# conditioning_circuit.net
KiCad netlist of a schematic drawn in Altium Designer
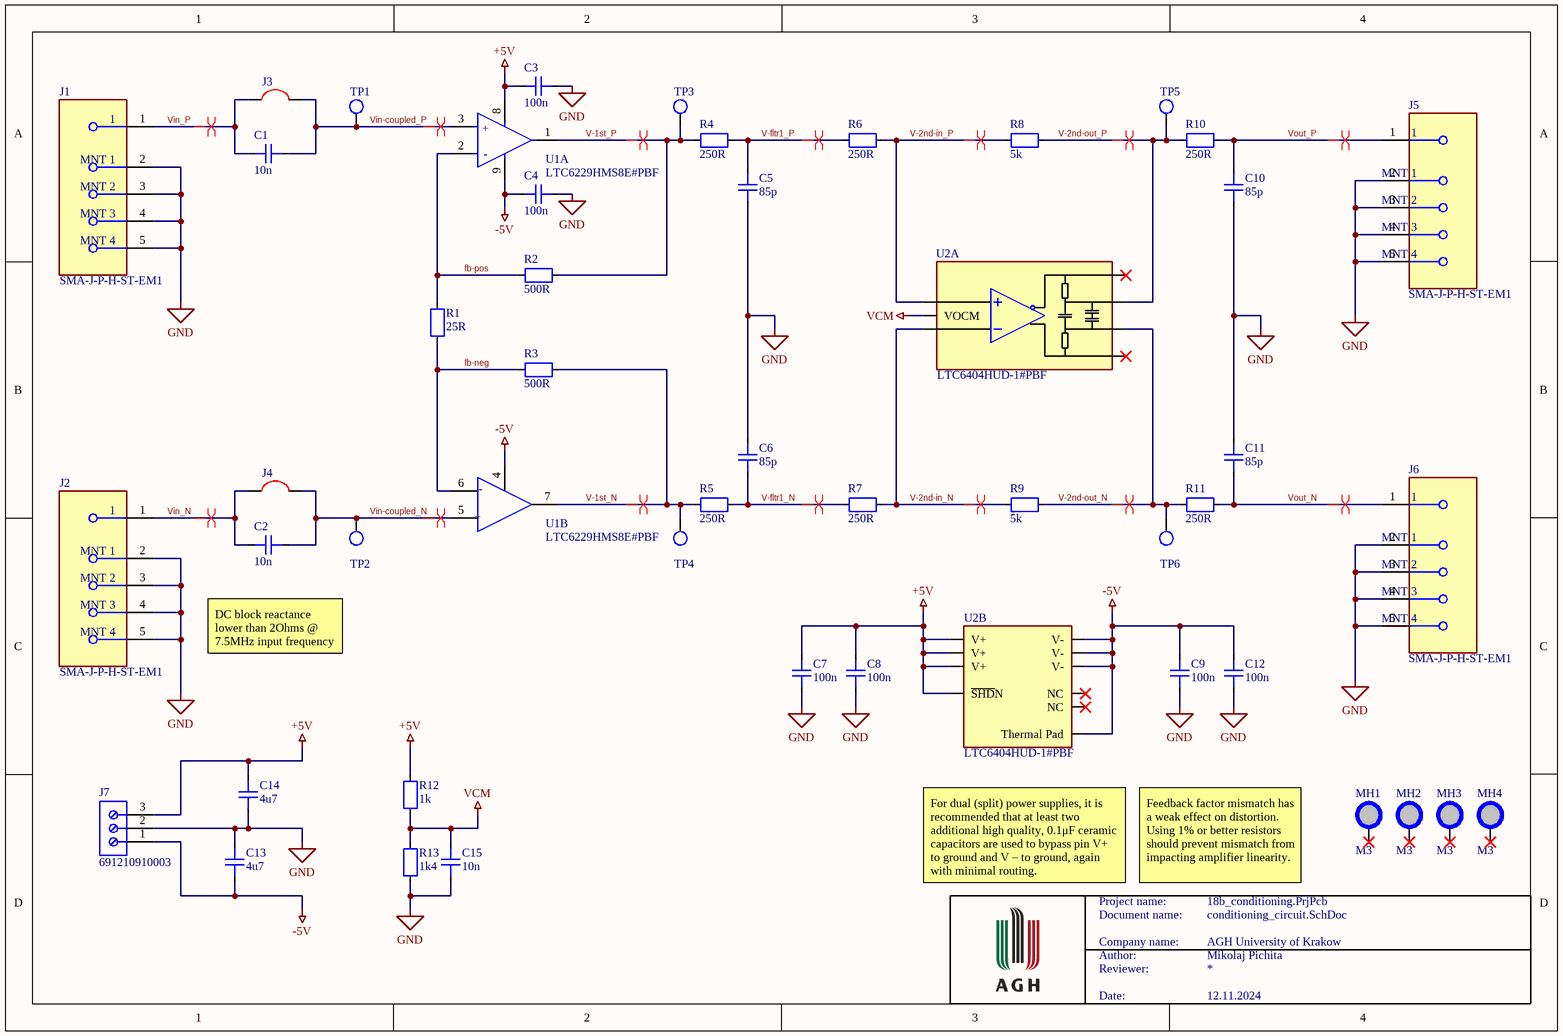
[diagram p0: conditioning_circuit.SchDoc]

(export (version "E")
  (design (tool "Eeschema 10.0.6"))
  (components
    (comp (ref "C1")
      (value "10n")
      (footprint "CAP0603")
      (libsource (lib "Integrated_Library_main") (part "Capacitor"))
    )
    (comp (ref "C2")
      (value "10n")
      (footprint "CAP0603")
      (libsource (lib "Integrated_Library_main") (part "Capacitor"))
    )
    (comp (ref "C3")
      (value "100n")
      (footprint "CAP0603")
      (libsource (lib "Integrated_Library_main") (part "Capacitor"))
    )
    (comp (ref "C4")
      (value "100n")
      (footprint "CAP0603")
      (libsource (lib "Integrated_Library_main") (part "Capacitor"))
    )
    (comp (ref "C5")
      (value "85p")
      (footprint "CAP0603")
      (libsource (lib "Integrated_Library_main") (part "Capacitor"))
    )
    (comp (ref "C6")
      (value "85p")
      (footprint "CAP0603")
      (libsource (lib "Integrated_Library_main") (part "Capacitor"))
    )
    (comp (ref "C7")
      (value "100n")
      (footprint "CAP0603")
      (libsource (lib "Integrated_Library_main") (part "Capacitor"))
    )
    (comp (ref "C8")
      (value "100n")
      (footprint "CAP0603")
      (libsource (lib "Integrated_Library_main") (part "Capacitor"))
    )
    (comp (ref "C9")
      (value "100n")
      (footprint "CAP0603")
      (libsource (lib "Integrated_Library_main") (part "Capacitor"))
    )
    (comp (ref "C10")
      (value "85p")
      (footprint "CAP0603")
      (libsource (lib "Integrated_Library_main") (part "Capacitor"))
    )
    (comp (ref "C11")
      (value "85p")
      (footprint "CAP0603")
      (libsource (lib "Integrated_Library_main") (part "Capacitor"))
    )
    (comp (ref "C12")
      (value "100n")
      (footprint "CAP0603")
      (libsource (lib "Integrated_Library_main") (part "Capacitor"))
    )
    (comp (ref "C13")
      (value "4u7")
      (footprint "CAP0603")
      (libsource (lib "Integrated_Library_main") (part "Capacitor"))
    )
    (comp (ref "C14")
      (value "4u7")
      (footprint "CAP0603")
      (libsource (lib "Integrated_Library_main") (part "Capacitor"))
    )
    (comp (ref "C15")
      (value "10n")
      (footprint "CAP0603")
      (libsource (lib "Integrated_Library_main") (part "Capacitor"))
    )
    (comp (ref "J1")
      (value "SMA-J-P-H-ST-EM1")
      (footprint "FP-SMA-J-P-H-ST-EM1-MFG")
      (description "CONN SMA JACK STR 50OHM EDGE MNT")
      (libsource (lib "Altium Content Vault") (part "c65b8a639cdaef1819ea20b5466f8fa"))
    )
    (comp (ref "J2")
      (value "SMA-J-P-H-ST-EM1")
      (footprint "FP-SMA-J-P-H-ST-EM1-MFG")
      (description "CONN SMA JACK STR 50OHM EDGE MNT")
      (libsource (lib "Altium Content Vault") (part "c65b8a639cdaef1819ea20b5466f8fa"))
    )
    (comp (ref "J3")
      (value "*")
      (footprint "JUMPER")
      (libsource (lib "Integrated_Library_main") (part "Jumper"))
    )
    (comp (ref "J4")
      (value "*")
      (footprint "JUMPER")
      (libsource (lib "Integrated_Library_main") (part "Jumper"))
    )
    (comp (ref "J5")
      (value "SMA-J-P-H-ST-EM1")
      (footprint "FP-SMA-J-P-H-ST-EM1-MFG")
      (description "CONN SMA JACK STR 50OHM EDGE MNT")
      (libsource (lib "") (part "c65b8a639cdaef1819ea20b5466f8fa_1"))
    )
    (comp (ref "J6")
      (value "SMA-J-P-H-ST-EM1")
      (footprint "FP-SMA-J-P-H-ST-EM1-MFG")
      (description "CONN SMA JACK STR 50OHM EDGE MNT")
      (libsource (lib "") (part "c65b8a639cdaef1819ea20b5466f8fa_1"))
    )
    (comp (ref "J7")
      (value "691210910003")
      (footprint "691210910003")
      (libsource (lib "Altium Content Vault") (part "TBL - 1R - 03P - Screw"))
    )
    (comp (ref "MH1")
      (value "M3")
      (footprint "MountingHole")
      (libsource (lib "Integrated_Library_main") (part "Mounting hole"))
    )
    (comp (ref "MH2")
      (value "M3")
      (footprint "MountingHole")
      (libsource (lib "Integrated_Library_main") (part "Mounting hole"))
    )
    (comp (ref "MH3")
      (value "M3")
      (footprint "MountingHole")
      (libsource (lib "Integrated_Library_main") (part "Mounting hole"))
    )
    (comp (ref "MH4")
      (value "M3")
      (footprint "MountingHole")
      (libsource (lib "Integrated_Library_main") (part "Mounting hole"))
    )
    (comp (ref "R1")
      (value "25R")
      (footprint "RES0603")
      (libsource (lib "Integrated_Library_main") (part "Resistor"))
    )
    (comp (ref "R2")
      (value "500R")
      (footprint "RES0603")
      (libsource (lib "Integrated_Library_main") (part "Resistor"))
    )
    (comp (ref "R3")
      (value "500R")
      (footprint "RES0603")
      (libsource (lib "Integrated_Library_main") (part "Resistor"))
    )
    (comp (ref "R4")
      (value "250R")
      (footprint "RES0603")
      (libsource (lib "Integrated_Library_main") (part "Resistor"))
    )
    (comp (ref "R5")
      (value "250R")
      (footprint "RES0603")
      (libsource (lib "Integrated_Library_main") (part "Resistor"))
    )
    (comp (ref "R6")
      (value "250R")
      (footprint "RES0603")
      (libsource (lib "Integrated_Library_main") (part "Resistor"))
    )
    (comp (ref "R7")
      (value "250R")
      (footprint "RES0603")
      (libsource (lib "Integrated_Library_main") (part "Resistor"))
    )
    (comp (ref "R8")
      (value "5k")
      (footprint "RES0603")
      (libsource (lib "Integrated_Library_main") (part "Resistor"))
    )
    (comp (ref "R9")
      (value "5k")
      (footprint "RES0603")
      (libsource (lib "Integrated_Library_main") (part "Resistor"))
    )
    (comp (ref "R10")
      (value "250R")
      (footprint "RES0603")
      (libsource (lib "Integrated_Library_main") (part "Resistor"))
    )
    (comp (ref "R11")
      (value "250R")
      (footprint "RES0603")
      (libsource (lib "Integrated_Library_main") (part "Resistor"))
    )
    (comp (ref "R12")
      (value "1k")
      (footprint "RES0603")
      (libsource (lib "Integrated_Library_main") (part "Resistor"))
    )
    (comp (ref "R13")
      (value "1k4")
      (footprint "RES0603")
      (libsource (lib "Integrated_Library_main") (part "Resistor"))
    )
    (comp (ref "TP1")
      (value "Testpoint")
      (footprint "SMD_TESTPOINT")
      (libsource (lib "Integrated_Library_main") (part "SMD_testpoint"))
    )
    (comp (ref "TP2")
      (value "Testpoint")
      (footprint "SMD_TESTPOINT")
      (libsource (lib "Integrated_Library_main") (part "SMD_testpoint"))
    )
    (comp (ref "TP3")
      (value "Testpoint")
      (footprint "SMD_TESTPOINT")
      (libsource (lib "Integrated_Library_main") (part "SMD_testpoint"))
    )
    (comp (ref "TP4")
      (value "Testpoint")
      (footprint "SMD_TESTPOINT")
      (libsource (lib "Integrated_Library_main") (part "SMD_testpoint"))
    )
    (comp (ref "TP5")
      (value "Testpoint")
      (footprint "SMD_TESTPOINT")
      (libsource (lib "Integrated_Library_main") (part "SMD_testpoint"))
    )
    (comp (ref "TP6")
      (value "Testpoint")
      (footprint "SMD_TESTPOINT")
      (libsource (lib "Integrated_Library_main") (part "SMD_testpoint"))
    )
    (comp (ref "U1")
      (value "LTC6229HMS8E#PBF")
      (footprint "FP-MS8E-8-05-08-1662-IPC_C")
      (description "IC OPAMP GP 1 CIRCUIT 8MSOP")
      (libsource (lib "Altium Content Vault") (part "d9671d919594e6673b65f0ad0d835fa"))
    )
    (comp (ref "U2")
      (value "LTC6404HUD-1#PBF")
      (footprint "LT-UD-16_M")
      (description "High Speed Operational Amplifiers 600MHz, L N, Hi Prec Fully Diff In/Out A")
      (libsource (lib "") (part "LTC6404HUD-1#PBF_1"))
    )
  )
  (nets
    (net (code "1") (name "+5V") (class "Default")
      (node (ref "C14") (pin "1") (pintype "passive"))
      (node (ref "C3") (pin "1") (pintype "passive"))
      (node (ref "C7") (pin "1") (pintype "passive"))
      (node (ref "C8") (pin "1") (pintype "passive"))
      (node (ref "J7") (pin "3") (pinfunction "3_3") (pintype "passive"))
      (node (ref "R12") (pin "2") (pintype "passive"))
      (node (ref "U1") (pin "8") (pinfunction "V+_8") (pintype "power_in"))
      (node (ref "U2") (pin "1") (pinfunction "~{SHD}N_1") (pintype "passive"))
      (node (ref "U2") (pin "10") (pinfunction "V+_10") (pintype "passive"))
      (node (ref "U2") (pin "11") (pinfunction "V+_11") (pintype "passive"))
      (node (ref "U2") (pin "2") (pinfunction "V+_2") (pintype "passive"))
    )
    (net (code "2") (name "-5V") (class "Default")
      (node (ref "C12") (pin "1") (pintype "passive"))
      (node (ref "C13") (pin "2") (pintype "passive"))
      (node (ref "C4") (pin "1") (pintype "passive"))
      (node (ref "C9") (pin "1") (pintype "passive"))
      (node (ref "J7") (pin "1") (pinfunction "1_1") (pintype "passive"))
      (node (ref "U1") (pin "4") (pinfunction "V-_4") (pintype "power_in"))
      (node (ref "U1") (pin "9") (pinfunction "V-_9") (pintype "power_in"))
      (node (ref "U2") (pin "12") (pinfunction "V-_12") (pintype "passive"))
      (node (ref "U2") (pin "17") (pinfunction "Thermal_Pad_17") (pintype "passive"))
      (node (ref "U2") (pin "3") (pinfunction "V-_3") (pintype "passive"))
      (node (ref "U2") (pin "9") (pinfunction "V-_9") (pintype "passive"))
    )
    (net (code "3") (name "/V-1st_N") (class "Default")
      (node (ref "R3") (pin "2") (pintype "passive"))
      (node (ref "R5") (pin "2") (pintype "passive"))
      (node (ref "TP4") (pin "1") (pintype "passive"))
      (node (ref "U1") (pin "7") (pinfunction "OUTB_7") (pintype "passive"))
    )
    (net (code "4") (name "/V-1st_P") (class "Default")
      (node (ref "R2") (pin "2") (pintype "passive"))
      (node (ref "R4") (pin "1") (pintype "passive"))
      (node (ref "TP3") (pin "1") (pintype "passive"))
      (node (ref "U1") (pin "1") (pinfunction "OUTA_1") (pintype "passive"))
    )
    (net (code "5") (name "/V-2nd-in_N") (class "Default")
      (node (ref "R7") (pin "1") (pintype "passive"))
      (node (ref "R9") (pin "1") (pintype "passive"))
      (node (ref "U2") (pin "6") (pinfunction "IN-_6") (pintype "passive"))
    )
    (net (code "6") (name "/V-2nd-in_P") (class "Default")
      (node (ref "R6") (pin "2") (pintype "passive"))
      (node (ref "R8") (pin "1") (pintype "passive"))
      (node (ref "U2") (pin "15") (pinfunction "IN+_15") (pintype "passive"))
    )
    (net (code "7") (name "/V-2nd-out_N") (class "Default")
      (node (ref "R11") (pin "2") (pintype "passive"))
      (node (ref "R9") (pin "2") (pintype "passive"))
      (node (ref "TP6") (pin "1") (pintype "passive"))
      (node (ref "U2") (pin "7") (pinfunction "OUT+_7") (pintype "passive"))
    )
    (net (code "8") (name "/V-2nd-out_P") (class "Default")
      (node (ref "R10") (pin "1") (pintype "passive"))
      (node (ref "R8") (pin "2") (pintype "passive"))
      (node (ref "TP5") (pin "1") (pintype "passive"))
      (node (ref "U2") (pin "14") (pinfunction "OUT-_14") (pintype "passive"))
    )
    (net (code "9") (name "/V-fltr1_N") (class "Default")
      (node (ref "C6") (pin "2") (pintype "passive"))
      (node (ref "R5") (pin "1") (pintype "passive"))
      (node (ref "R7") (pin "2") (pintype "passive"))
    )
    (net (code "10") (name "/V-fltr1_P") (class "Default")
      (node (ref "C5") (pin "2") (pintype "passive"))
      (node (ref "R4") (pin "2") (pintype "passive"))
      (node (ref "R6") (pin "1") (pintype "passive"))
    )
    (net (code "11") (name "/Vin-coupled_N") (class "Default")
      (node (ref "C2") (pin "2") (pintype "passive"))
      (node (ref "J4") (pin "2") (pinfunction "2_2") (pintype "passive"))
      (node (ref "TP2") (pin "1") (pintype "passive"))
      (node (ref "U1") (pin "5") (pinfunction "+INB_5") (pintype "tri_state"))
    )
    (net (code "12") (name "/Vin-coupled_P") (class "Default")
      (node (ref "C1") (pin "2") (pintype "passive"))
      (node (ref "J3") (pin "2") (pinfunction "2_2") (pintype "passive"))
      (node (ref "TP1") (pin "1") (pintype "passive"))
      (node (ref "U1") (pin "3") (pinfunction "+IN_A_3") (pintype "tri_state"))
    )
    (net (code "13") (name "/Vin_N") (class "Default")
      (node (ref "C2") (pin "1") (pintype "passive"))
      (node (ref "J2") (pin "1") (pinfunction "1_1") (pintype "passive"))
      (node (ref "J4") (pin "1") (pinfunction "1_1") (pintype "passive"))
    )
    (net (code "14") (name "/Vin_P") (class "Default")
      (node (ref "C1") (pin "1") (pintype "passive"))
      (node (ref "J1") (pin "1") (pinfunction "1_1") (pintype "passive"))
      (node (ref "J3") (pin "1") (pinfunction "1_1") (pintype "passive"))
    )
    (net (code "15") (name "/Vout_N") (class "Default")
      (node (ref "C11") (pin "2") (pintype "passive"))
      (node (ref "J6") (pin "1") (pinfunction "1_1") (pintype "passive"))
      (node (ref "R11") (pin "1") (pintype "passive"))
    )
    (net (code "16") (name "/Vout_P") (class "Default")
      (node (ref "C10") (pin "2") (pintype "passive"))
      (node (ref "J5") (pin "1") (pinfunction "1_1") (pintype "passive"))
      (node (ref "R10") (pin "2") (pintype "passive"))
    )
    (net (code "17") (name "/fb-neg") (class "Default")
      (node (ref "R1") (pin "2") (pintype "passive"))
      (node (ref "R3") (pin "1") (pintype "passive"))
      (node (ref "U1") (pin "6") (pinfunction "-INB_6") (pintype "tri_state"))
    )
    (net (code "18") (name "/fb-pos") (class "Default")
      (node (ref "R1") (pin "1") (pintype "passive"))
      (node (ref "R2") (pin "1") (pintype "passive"))
      (node (ref "U1") (pin "2") (pinfunction "-IN_A_2") (pintype "tri_state"))
    )
    (net (code "19") (name "GND") (class "Default")
      (node (ref "C10") (pin "1") (pintype "passive"))
      (node (ref "C11") (pin "1") (pintype "passive"))
      (node (ref "C12") (pin "2") (pintype "passive"))
      (node (ref "C13") (pin "1") (pintype "passive"))
      (node (ref "C14") (pin "2") (pintype "passive"))
      (node (ref "C15") (pin "2") (pintype "passive"))
      (node (ref "C3") (pin "2") (pintype "passive"))
      (node (ref "C4") (pin "2") (pintype "passive"))
      (node (ref "C5") (pin "1") (pintype "passive"))
      (node (ref "C6") (pin "1") (pintype "passive"))
      (node (ref "C7") (pin "2") (pintype "passive"))
      (node (ref "C8") (pin "2") (pintype "passive"))
      (node (ref "C9") (pin "2") (pintype "passive"))
      (node (ref "J1") (pin "2") (pinfunction "MNT_1_2") (pintype "passive"))
      (node (ref "J1") (pin "3") (pinfunction "MNT_2_3") (pintype "passive"))
      (node (ref "J1") (pin "4") (pinfunction "MNT_3_4") (pintype "passive"))
      (node (ref "J1") (pin "5") (pinfunction "MNT_4_5") (pintype "passive"))
      (node (ref "J2") (pin "2") (pinfunction "MNT_1_2") (pintype "passive"))
      (node (ref "J2") (pin "3") (pinfunction "MNT_2_3") (pintype "passive"))
      (node (ref "J2") (pin "4") (pinfunction "MNT_3_4") (pintype "passive"))
      (node (ref "J2") (pin "5") (pinfunction "MNT_4_5") (pintype "passive"))
      (node (ref "J5") (pin "2") (pinfunction "MNT_1_2") (pintype "passive"))
      (node (ref "J5") (pin "3") (pinfunction "MNT_2_3") (pintype "passive"))
      (node (ref "J5") (pin "4") (pinfunction "MNT_3_4") (pintype "passive"))
      (node (ref "J5") (pin "5") (pinfunction "MNT_4_5") (pintype "passive"))
      (node (ref "J6") (pin "2") (pinfunction "MNT_1_2") (pintype "passive"))
      (node (ref "J6") (pin "3") (pinfunction "MNT_2_3") (pintype "passive"))
      (node (ref "J6") (pin "4") (pinfunction "MNT_3_4") (pintype "passive"))
      (node (ref "J6") (pin "5") (pinfunction "MNT_4_5") (pintype "passive"))
      (node (ref "J7") (pin "2") (pinfunction "2_2") (pintype "passive"))
      (node (ref "R13") (pin "1") (pintype "passive"))
    )
    (net (code "20") (name "VCM") (class "Default")
      (node (ref "C15") (pin "1") (pintype "passive"))
      (node (ref "R12") (pin "1") (pintype "passive"))
      (node (ref "R13") (pin "2") (pintype "passive"))
      (node (ref "U2") (pin "4") (pinfunction "VOCM_4") (pintype "passive"))
    )
    (net (code "21") (name "unconnected-(MH1-Pad1)") (class "Default")
      (node (ref "MH1") (pin "1") (pintype "passive+no_connect"))
    )
    (net (code "22") (name "unconnected-(MH2-Pad1)") (class "Default")
      (node (ref "MH2") (pin "1") (pintype "passive+no_connect"))
    )
    (net (code "23") (name "unconnected-(MH3-Pad1)") (class "Default")
      (node (ref "MH3") (pin "1") (pintype "passive+no_connect"))
    )
    (net (code "24") (name "unconnected-(MH4-Pad1)") (class "Default")
      (node (ref "MH4") (pin "1") (pintype "passive+no_connect"))
    )
    (net (code "25") (name "unconnected-(U2A-OUTF+-Pad8)") (class "Default")
      (node (ref "U2") (pin "8") (pinfunction "OUTF+_8") (pintype "passive+no_connect"))
    )
    (net (code "26") (name "unconnected-(U2A-OUTF--Pad13)") (class "Default")
      (node (ref "U2") (pin "13") (pinfunction "OUTF-_13") (pintype "passive+no_connect"))
    )
    (net (code "27") (name "unconnected-(U2B-NC-Pad5)") (class "Default")
      (node (ref "U2") (pin "5") (pinfunction "NC_5") (pintype "passive+no_connect"))
    )
    (net (code "28") (name "unconnected-(U2B-NC-Pad16)") (class "Default")
      (node (ref "U2") (pin "16") (pinfunction "NC_16") (pintype "passive+no_connect"))
    )
  )
)
